# SparkFun_MegaShield.net
KiCad netlist of a schematic drawn in EAGLE
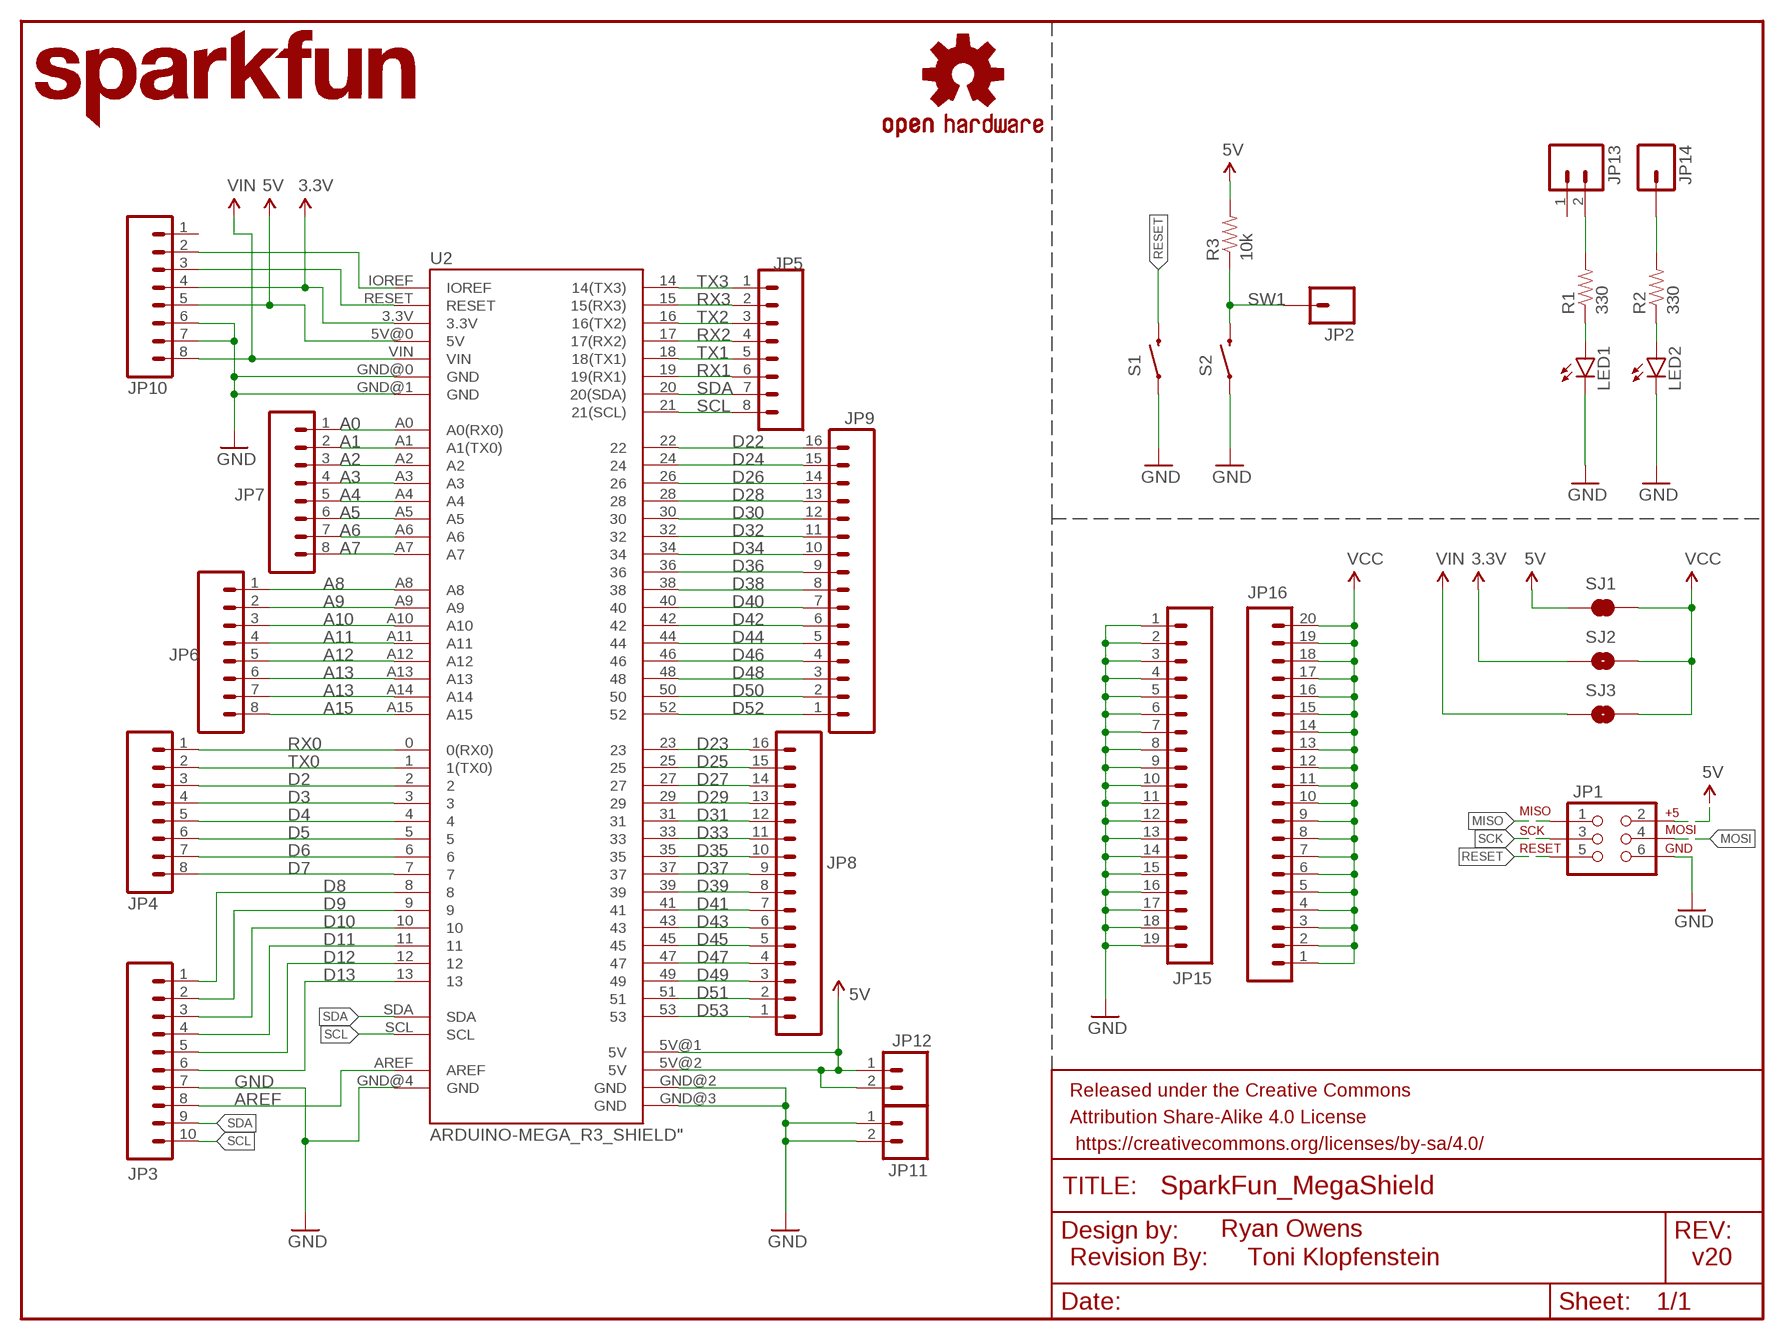
[diagram p0: schematic, sheet 1]

(export (version "E")
  (design (tool "Eeschema 10.0.6"))
  (components
    (comp (ref "FRAME1")
      (value "FRAME-LETTER")
      (footprint "eagle-import:CREATIVE_COMMONS")
      (libsource (lib "eagle-import") (part "FRAME-LETTER"))
    )
    (comp (ref "JP1")
      (value "AVR_SPI_PRG_6PTH")
      (footprint "eagle-import:2X3")
      (libsource (lib "eagle-import") (part "AVR_SPI_PRG_6PTH"))
    )
    (comp (ref "JP2")
      (value "M01PTH")
      (footprint "eagle-import:1X01")
      (libsource (lib "eagle-import") (part "M01PTH"))
    )
    (comp (ref "JP3")
      (value "M10SILK_FEMALE_PTH")
      (footprint "eagle-import:1X10")
      (libsource (lib "eagle-import") (part "M10SILK_FEMALE_PTH"))
    )
    (comp (ref "JP4")
      (value "M08")
      (footprint "eagle-import:1X08_ROUND")
      (libsource (lib "eagle-import") (part "M08"))
    )
    (comp (ref "JP5")
      (value "M08")
      (footprint "eagle-import:1X08_ROUND")
      (libsource (lib "eagle-import") (part "M08"))
    )
    (comp (ref "JP6")
      (value "M08")
      (footprint "eagle-import:1X08_ROUND")
      (libsource (lib "eagle-import") (part "M08"))
    )
    (comp (ref "JP7")
      (value "M08")
      (footprint "eagle-import:1X08_ROUND")
      (libsource (lib "eagle-import") (part "M08"))
    )
    (comp (ref "JP8")
      (value "M16PTH")
      (footprint "eagle-import:1X16")
      (libsource (lib "eagle-import") (part "M16PTH"))
    )
    (comp (ref "JP9")
      (value "M16PTH")
      (footprint "eagle-import:1X16")
      (libsource (lib "eagle-import") (part "M16PTH"))
    )
    (comp (ref "JP10")
      (value "M08")
      (footprint "eagle-import:1X08_ROUND")
      (libsource (lib "eagle-import") (part "M08"))
    )
    (comp (ref "JP11")
      (value "M02PTH")
      (footprint "eagle-import:1X02")
      (libsource (lib "eagle-import") (part "M02PTH"))
    )
    (comp (ref "JP12")
      (value "M02PTH")
      (footprint "eagle-import:1X02")
      (libsource (lib "eagle-import") (part "M02PTH"))
    )
    (comp (ref "JP13")
      (value "M02PTH")
      (footprint "eagle-import:1X02")
      (libsource (lib "eagle-import") (part "M02PTH"))
    )
    (comp (ref "JP14")
      (value "M01PTH")
      (footprint "eagle-import:1X01")
      (libsource (lib "eagle-import") (part "M01PTH"))
    )
    (comp (ref "JP15")
      (value "M191X19")
      (footprint "eagle-import:1X19")
      (libsource (lib "eagle-import") (part "M191X19"))
    )
    (comp (ref "JP16")
      (value "M20")
      (footprint "eagle-import:1X20")
      (libsource (lib "eagle-import") (part "M20"))
    )
    (comp (ref "LED1")
      (value "Red")
      (footprint "eagle-import:LED3MM")
      (libsource (lib "eagle-import") (part "LED3MM"))
    )
    (comp (ref "LED2")
      (value "Green")
      (footprint "eagle-import:LED3MM")
      (libsource (lib "eagle-import") (part "LED3MM"))
    )
    (comp (ref "LOGO1")
      (value "OSHW-LOGOS")
      (footprint "eagle-import:OSHW-LOGO-S")
      (libsource (lib "eagle-import") (part "OSHW-LOGOS"))
    )
    (comp (ref "LOGO2")
      (value "SFE_LOGO_NAME.1_INCH")
      (footprint "eagle-import:SFE_LOGO_NAME_.1")
      (libsource (lib "eagle-import") (part "SFE_LOGO_NAME.1_INCH"))
    )
    (comp (ref "R1")
      (value "330")
      (footprint "eagle-import:AXIAL-0.3")
      (libsource (lib "eagle-import") (part "RESISTORPTH1"))
    )
    (comp (ref "R2")
      (value "330")
      (footprint "eagle-import:AXIAL-0.3")
      (libsource (lib "eagle-import") (part "RESISTORPTH1"))
    )
    (comp (ref "R3")
      (value "10k")
      (footprint "eagle-import:AXIAL-0.3")
      (libsource (lib "eagle-import") (part "RESISTORPTH1"))
    )
    (comp (ref "S1")
      (value "SWITCH-MOMENTARY-2PTH")
      (footprint "eagle-import:TACTILE-PTH")
      (libsource (lib "eagle-import") (part "SWITCH-MOMENTARY-2PTH"))
    )
    (comp (ref "S2")
      (value "SWITCH-MOMENTARY-2PTH")
      (footprint "eagle-import:TACTILE-PTH")
      (libsource (lib "eagle-import") (part "SWITCH-MOMENTARY-2PTH"))
    )
    (comp (ref "SJ1")
      (value "JUMPER-PAD-2-NC_BY_TRACE")
      (footprint "eagle-import:PAD-JUMPER-2-NC_BY_TRACE_YES_SILK")
      (libsource (lib "eagle-import") (part "JUMPER-PAD-2-NC_BY_TRACE"))
    )
    (comp (ref "SJ2")
      (value "JUMPER-PAD-2-NOYES_SILK")
      (footprint "eagle-import:PAD-JUMPER-2-NO_YES_SILK")
      (libsource (lib "eagle-import") (part "JUMPER-PAD-2-NOYES_SILK"))
    )
    (comp (ref "SJ3")
      (value "JUMPER-PAD-2-NOYES_SILK")
      (footprint "eagle-import:PAD-JUMPER-2-NO_YES_SILK")
      (libsource (lib "eagle-import") (part "JUMPER-PAD-2-NOYES_SILK"))
    )
    (comp (ref "U$3")
      (value "REVISION")
      (footprint "eagle-import:REVISION")
      (libsource (lib "eagle-import") (part "REVISION"))
    )
    (comp (ref "U2")
      (value "ARDUINO-MEGA_R3_SHIELD\"")
      (footprint "eagle-import:ARDUINO_MEGA_R3_OUTLINE")
      (libsource (lib "eagle-import") (part "ARDUINO-MEGA_R3_SHIELD{dblquote}"))
    )
  )
  (nets
    (net (code "1") (name "/A0") (class "Default")
      (node (ref "JP7") (pin "1") (pinfunction "1_1") (pintype "passive"))
      (node (ref "U2") (pin "A0") (pinfunction "A0(RX0)_A0") (pintype "bidirectional"))
    )
    (net (code "2") (name "/A1") (class "Default")
      (node (ref "JP7") (pin "2") (pinfunction "2_2") (pintype "passive"))
      (node (ref "U2") (pin "A1") (pinfunction "A1(TX0)_A1") (pintype "bidirectional"))
    )
    (net (code "3") (name "/A2") (class "Default")
      (node (ref "JP7") (pin "3") (pinfunction "3_3") (pintype "passive"))
      (node (ref "U2") (pin "A2") (pinfunction "A2_A2") (pintype "bidirectional"))
    )
    (net (code "4") (name "/A3") (class "Default")
      (node (ref "JP7") (pin "4") (pinfunction "4_4") (pintype "passive"))
      (node (ref "U2") (pin "A3") (pinfunction "A3_A3") (pintype "bidirectional"))
    )
    (net (code "5") (name "/A4") (class "Default")
      (node (ref "JP7") (pin "5") (pinfunction "5_5") (pintype "passive"))
      (node (ref "U2") (pin "A4") (pinfunction "A4_A4") (pintype "bidirectional"))
    )
    (net (code "6") (name "/A5") (class "Default")
      (node (ref "JP7") (pin "6") (pinfunction "6_6") (pintype "passive"))
      (node (ref "U2") (pin "A5") (pinfunction "A5_A5") (pintype "bidirectional"))
    )
    (net (code "7") (name "/A6") (class "Default")
      (node (ref "JP7") (pin "7") (pinfunction "7_7") (pintype "passive"))
      (node (ref "U2") (pin "A6") (pinfunction "A6_A6") (pintype "bidirectional"))
    )
    (net (code "8") (name "/A7") (class "Default")
      (node (ref "JP7") (pin "8") (pinfunction "8_8") (pintype "passive"))
      (node (ref "U2") (pin "A7") (pinfunction "A7_A7") (pintype "bidirectional"))
    )
    (net (code "9") (name "/A8") (class "Default")
      (node (ref "JP6") (pin "1") (pinfunction "1_1") (pintype "passive"))
      (node (ref "U2") (pin "A8") (pinfunction "A8_A8") (pintype "bidirectional"))
    )
    (net (code "10") (name "/A9") (class "Default")
      (node (ref "JP6") (pin "2") (pinfunction "2_2") (pintype "passive"))
      (node (ref "U2") (pin "A9") (pinfunction "A9_A9") (pintype "bidirectional"))
    )
    (net (code "11") (name "/A10") (class "Default")
      (node (ref "JP6") (pin "3") (pinfunction "3_3") (pintype "passive"))
      (node (ref "U2") (pin "A10") (pinfunction "A10_A10") (pintype "bidirectional"))
    )
    (net (code "12") (name "/A11") (class "Default")
      (node (ref "JP6") (pin "4") (pinfunction "4_4") (pintype "passive"))
      (node (ref "U2") (pin "A11") (pinfunction "A11_A11") (pintype "bidirectional"))
    )
    (net (code "13") (name "/A12") (class "Default")
      (node (ref "JP6") (pin "5") (pinfunction "5_5") (pintype "passive"))
      (node (ref "U2") (pin "A12") (pinfunction "A12_A12") (pintype "bidirectional"))
    )
    (net (code "14") (name "/A13") (class "Default")
      (node (ref "JP6") (pin "6") (pinfunction "6_6") (pintype "passive"))
      (node (ref "U2") (pin "A13") (pinfunction "A13_A13") (pintype "bidirectional"))
    )
    (net (code "15") (name "/A15") (class "Default")
      (node (ref "JP6") (pin "8") (pinfunction "8_8") (pintype "passive"))
      (node (ref "U2") (pin "A15") (pinfunction "A15_A15") (pintype "bidirectional"))
    )
    (net (code "16") (name "/AREF") (class "Default")
      (node (ref "JP3") (pin "8") (pinfunction "8_8") (pintype "passive"))
      (node (ref "U2") (pin "AREF") (pinfunction "AREF_AREF") (pintype "bidirectional"))
    )
    (net (code "17") (name "/D2") (class "Default")
      (node (ref "JP4") (pin "3") (pinfunction "3_3") (pintype "passive"))
      (node (ref "U2") (pin "2") (pinfunction "2_2") (pintype "bidirectional"))
    )
    (net (code "18") (name "/D3") (class "Default")
      (node (ref "JP4") (pin "4") (pinfunction "4_4") (pintype "passive"))
      (node (ref "U2") (pin "3") (pinfunction "3_3") (pintype "bidirectional"))
    )
    (net (code "19") (name "/D4") (class "Default")
      (node (ref "JP4") (pin "5") (pinfunction "5_5") (pintype "passive"))
      (node (ref "U2") (pin "4") (pinfunction "4_4") (pintype "bidirectional"))
    )
    (net (code "20") (name "/D5") (class "Default")
      (node (ref "JP4") (pin "6") (pinfunction "6_6") (pintype "passive"))
      (node (ref "U2") (pin "5") (pinfunction "5_5") (pintype "bidirectional"))
    )
    (net (code "21") (name "/D6") (class "Default")
      (node (ref "JP4") (pin "7") (pinfunction "7_7") (pintype "passive"))
      (node (ref "U2") (pin "6") (pinfunction "6_6") (pintype "bidirectional"))
    )
    (net (code "22") (name "/D7") (class "Default")
      (node (ref "JP4") (pin "8") (pinfunction "8_8") (pintype "passive"))
      (node (ref "U2") (pin "7") (pinfunction "7_7") (pintype "bidirectional"))
    )
    (net (code "23") (name "/D8") (class "Default")
      (node (ref "JP3") (pin "1") (pinfunction "1_1") (pintype "passive"))
      (node (ref "U2") (pin "8") (pinfunction "8_8") (pintype "bidirectional"))
    )
    (net (code "24") (name "/D9") (class "Default")
      (node (ref "JP3") (pin "2") (pinfunction "2_2") (pintype "passive"))
      (node (ref "U2") (pin "9") (pinfunction "9_9") (pintype "bidirectional"))
    )
    (net (code "25") (name "/D10") (class "Default")
      (node (ref "JP3") (pin "3") (pinfunction "3_3") (pintype "passive"))
      (node (ref "U2") (pin "10") (pinfunction "10_10") (pintype "bidirectional"))
    )
    (net (code "26") (name "/D11") (class "Default")
      (node (ref "JP3") (pin "4") (pinfunction "4_4") (pintype "passive"))
      (node (ref "U2") (pin "11") (pinfunction "11_11") (pintype "bidirectional"))
    )
    (net (code "27") (name "/D12") (class "Default")
      (node (ref "JP3") (pin "5") (pinfunction "5_5") (pintype "passive"))
      (node (ref "U2") (pin "12") (pinfunction "12_12") (pintype "bidirectional"))
    )
    (net (code "28") (name "/D13") (class "Default")
      (node (ref "JP3") (pin "6") (pinfunction "6_6") (pintype "passive"))
      (node (ref "U2") (pin "13") (pinfunction "13_13") (pintype "bidirectional"))
    )
    (net (code "29") (name "/D22") (class "Default")
      (node (ref "JP9") (pin "16") (pinfunction "16_16") (pintype "passive"))
      (node (ref "U2") (pin "22") (pinfunction "22_22") (pintype "bidirectional"))
    )
    (net (code "30") (name "/D23") (class "Default")
      (node (ref "JP8") (pin "16") (pinfunction "16_16") (pintype "passive"))
      (node (ref "U2") (pin "23") (pinfunction "23_23") (pintype "bidirectional"))
    )
    (net (code "31") (name "/D24") (class "Default")
      (node (ref "JP9") (pin "15") (pinfunction "15_15") (pintype "passive"))
      (node (ref "U2") (pin "24") (pinfunction "24_24") (pintype "bidirectional"))
    )
    (net (code "32") (name "/D25") (class "Default")
      (node (ref "JP8") (pin "15") (pinfunction "15_15") (pintype "passive"))
      (node (ref "U2") (pin "25") (pinfunction "25_25") (pintype "bidirectional"))
    )
    (net (code "33") (name "/D26") (class "Default")
      (node (ref "JP9") (pin "14") (pinfunction "14_14") (pintype "passive"))
      (node (ref "U2") (pin "26") (pinfunction "26_26") (pintype "bidirectional"))
    )
    (net (code "34") (name "/D27") (class "Default")
      (node (ref "JP8") (pin "14") (pinfunction "14_14") (pintype "passive"))
      (node (ref "U2") (pin "27") (pinfunction "27_27") (pintype "bidirectional"))
    )
    (net (code "35") (name "/D28") (class "Default")
      (node (ref "JP9") (pin "13") (pinfunction "13_13") (pintype "passive"))
      (node (ref "U2") (pin "28") (pinfunction "28_28") (pintype "bidirectional"))
    )
    (net (code "36") (name "/D29") (class "Default")
      (node (ref "JP8") (pin "13") (pinfunction "13_13") (pintype "passive"))
      (node (ref "U2") (pin "29") (pinfunction "29_29") (pintype "bidirectional"))
    )
    (net (code "37") (name "/D30") (class "Default")
      (node (ref "JP9") (pin "12") (pinfunction "12_12") (pintype "passive"))
      (node (ref "U2") (pin "30") (pinfunction "30_30") (pintype "bidirectional"))
    )
    (net (code "38") (name "/D31") (class "Default")
      (node (ref "JP8") (pin "12") (pinfunction "12_12") (pintype "passive"))
      (node (ref "U2") (pin "31") (pinfunction "31_31") (pintype "bidirectional"))
    )
    (net (code "39") (name "/D32") (class "Default")
      (node (ref "JP9") (pin "11") (pinfunction "11_11") (pintype "passive"))
      (node (ref "U2") (pin "32") (pinfunction "32_32") (pintype "bidirectional"))
    )
    (net (code "40") (name "/D33") (class "Default")
      (node (ref "JP8") (pin "11") (pinfunction "11_11") (pintype "passive"))
      (node (ref "U2") (pin "33") (pinfunction "33_33") (pintype "bidirectional"))
    )
    (net (code "41") (name "/D34") (class "Default")
      (node (ref "JP9") (pin "10") (pinfunction "10_10") (pintype "passive"))
      (node (ref "U2") (pin "34") (pinfunction "34_34") (pintype "bidirectional"))
    )
    (net (code "42") (name "/D35") (class "Default")
      (node (ref "JP8") (pin "10") (pinfunction "10_10") (pintype "passive"))
      (node (ref "U2") (pin "35") (pinfunction "35_35") (pintype "bidirectional"))
    )
    (net (code "43") (name "/D36") (class "Default")
      (node (ref "JP9") (pin "9") (pinfunction "9_9") (pintype "passive"))
      (node (ref "U2") (pin "36") (pinfunction "36_36") (pintype "bidirectional"))
    )
    (net (code "44") (name "/D37") (class "Default")
      (node (ref "JP8") (pin "9") (pinfunction "9_9") (pintype "passive"))
      (node (ref "U2") (pin "37") (pinfunction "37_37") (pintype "bidirectional"))
    )
    (net (code "45") (name "/D38") (class "Default")
      (node (ref "JP9") (pin "8") (pinfunction "8_8") (pintype "passive"))
      (node (ref "U2") (pin "38") (pinfunction "38_38") (pintype "bidirectional"))
    )
    (net (code "46") (name "/D39") (class "Default")
      (node (ref "JP8") (pin "8") (pinfunction "8_8") (pintype "passive"))
      (node (ref "U2") (pin "39") (pinfunction "39_39") (pintype "bidirectional"))
    )
    (net (code "47") (name "/D40") (class "Default")
      (node (ref "JP9") (pin "7") (pinfunction "7_7") (pintype "passive"))
      (node (ref "U2") (pin "40") (pinfunction "40_40") (pintype "bidirectional"))
    )
    (net (code "48") (name "/D41") (class "Default")
      (node (ref "JP8") (pin "7") (pinfunction "7_7") (pintype "passive"))
      (node (ref "U2") (pin "41") (pinfunction "41_41") (pintype "bidirectional"))
    )
    (net (code "49") (name "/D42") (class "Default")
      (node (ref "JP9") (pin "6") (pinfunction "6_6") (pintype "passive"))
      (node (ref "U2") (pin "42") (pinfunction "42_42") (pintype "bidirectional"))
    )
    (net (code "50") (name "/D43") (class "Default")
      (node (ref "JP8") (pin "6") (pinfunction "6_6") (pintype "passive"))
      (node (ref "U2") (pin "43") (pinfunction "43_43") (pintype "bidirectional"))
    )
    (net (code "51") (name "/D44") (class "Default")
      (node (ref "JP9") (pin "5") (pinfunction "5_5") (pintype "passive"))
      (node (ref "U2") (pin "44") (pinfunction "44_44") (pintype "bidirectional"))
    )
    (net (code "52") (name "/D45") (class "Default")
      (node (ref "JP8") (pin "5") (pinfunction "5_5") (pintype "passive"))
      (node (ref "U2") (pin "45") (pinfunction "45_45") (pintype "bidirectional"))
    )
    (net (code "53") (name "/D46") (class "Default")
      (node (ref "JP9") (pin "4") (pinfunction "4_4") (pintype "passive"))
      (node (ref "U2") (pin "46") (pinfunction "46_46") (pintype "bidirectional"))
    )
    (net (code "54") (name "/D47") (class "Default")
      (node (ref "JP8") (pin "4") (pinfunction "4_4") (pintype "passive"))
      (node (ref "U2") (pin "47") (pinfunction "47_47") (pintype "bidirectional"))
    )
    (net (code "55") (name "/D48") (class "Default")
      (node (ref "JP9") (pin "3") (pinfunction "3_3") (pintype "passive"))
      (node (ref "U2") (pin "48") (pinfunction "48_48") (pintype "bidirectional"))
    )
    (net (code "56") (name "/D49") (class "Default")
      (node (ref "JP8") (pin "3") (pinfunction "3_3") (pintype "passive"))
      (node (ref "U2") (pin "49") (pinfunction "49_49") (pintype "bidirectional"))
    )
    (net (code "57") (name "/D50") (class "Default")
      (node (ref "JP9") (pin "2") (pinfunction "2_2") (pintype "passive"))
      (node (ref "U2") (pin "50") (pinfunction "50_50") (pintype "bidirectional"))
    )
    (net (code "58") (name "/D51") (class "Default")
      (node (ref "JP8") (pin "2") (pinfunction "2_2") (pintype "passive"))
      (node (ref "U2") (pin "51") (pinfunction "51_51") (pintype "bidirectional"))
    )
    (net (code "59") (name "/D52") (class "Default")
      (node (ref "JP9") (pin "1") (pinfunction "1_1") (pintype "passive"))
      (node (ref "U2") (pin "52") (pinfunction "52_52") (pintype "bidirectional"))
    )
    (net (code "60") (name "/D53") (class "Default")
      (node (ref "JP8") (pin "1") (pinfunction "1_1") (pintype "passive"))
      (node (ref "U2") (pin "53") (pinfunction "53_53") (pintype "bidirectional"))
    )
    (net (code "61") (name "/RX0") (class "Default")
      (node (ref "JP4") (pin "1") (pinfunction "1_1") (pintype "passive"))
      (node (ref "U2") (pin "0") (pinfunction "0(RX0)_0") (pintype "bidirectional"))
    )
    (net (code "62") (name "/RX1") (class "Default")
      (node (ref "JP5") (pin "6") (pinfunction "6_6") (pintype "passive"))
      (node (ref "U2") (pin "19") (pinfunction "19(RX1)_19") (pintype "bidirectional"))
    )
    (net (code "63") (name "/RX2") (class "Default")
      (node (ref "JP5") (pin "4") (pinfunction "4_4") (pintype "passive"))
      (node (ref "U2") (pin "17") (pinfunction "17(RX2)_17") (pintype "bidirectional"))
    )
    (net (code "64") (name "/RX3") (class "Default")
      (node (ref "JP5") (pin "2") (pinfunction "2_2") (pintype "passive"))
      (node (ref "U2") (pin "15") (pinfunction "15(RX3)_15") (pintype "bidirectional"))
    )
    (net (code "65") (name "/SW1") (class "Default")
      (node (ref "JP2") (pin "1") (pinfunction "1_1") (pintype "passive"))
      (node (ref "R3") (pin "P$1") (pinfunction "1_P$1") (pintype "passive"))
      (node (ref "S2") (pin "3") (pinfunction "2_3") (pintype "passive"))
    )
    (net (code "66") (name "/TX0") (class "Default")
      (node (ref "JP4") (pin "2") (pinfunction "2_2") (pintype "passive"))
      (node (ref "U2") (pin "1") (pinfunction "1(TX0)_1") (pintype "bidirectional"))
    )
    (net (code "67") (name "/TX1") (class "Default")
      (node (ref "JP5") (pin "5") (pinfunction "5_5") (pintype "passive"))
      (node (ref "U2") (pin "18") (pinfunction "18(TX1)_18") (pintype "bidirectional"))
    )
    (net (code "68") (name "/TX2") (class "Default")
      (node (ref "JP5") (pin "3") (pinfunction "3_3") (pintype "passive"))
      (node (ref "U2") (pin "16") (pinfunction "16(TX2)_16") (pintype "bidirectional"))
    )
    (net (code "69") (name "/TX3") (class "Default")
      (node (ref "JP5") (pin "1") (pinfunction "1_1") (pintype "passive"))
      (node (ref "U2") (pin "14") (pinfunction "14(TX3)_14") (pintype "bidirectional"))
    )
    (net (code "70") (name "3.3V") (class "Default")
      (node (ref "JP10") (pin "4") (pinfunction "4_4") (pintype "passive"))
      (node (ref "SJ2") (pin "1") (pinfunction "1_1") (pintype "passive"))
      (node (ref "U2") (pin "3.3V") (pinfunction "3.3V_3.3V") (pintype "bidirectional"))
    )
    (net (code "71") (name "5V") (class "Default")
      (node (ref "JP1") (pin "2") (pinfunction "2_2") (pintype "passive"))
      (node (ref "JP10") (pin "5") (pinfunction "5_5") (pintype "passive"))
      (node (ref "JP12") (pin "1") (pinfunction "1_1") (pintype "passive"))
      (node (ref "JP12") (pin "2") (pinfunction "2_2") (pintype "passive"))
      (node (ref "R3") (pin "P$2") (pinfunction "2_P$2") (pintype "passive"))
      (node (ref "SJ1") (pin "1") (pinfunction "1_1") (pintype "passive"))
      (node (ref "U2") (pin "5V@0") (pinfunction "5V_5V@0") (pintype "bidirectional"))
      (node (ref "U2") (pin "5V@1") (pinfunction "5V_5V@1") (pintype "bidirectional"))
      (node (ref "U2") (pin "5V@2") (pinfunction "5V_5V@2") (pintype "bidirectional"))
    )
    (net (code "72") (name "GND") (class "Default")
      (node (ref "JP1") (pin "6") (pinfunction "6_6") (pintype "passive"))
      (node (ref "JP10") (pin "6") (pinfunction "6_6") (pintype "passive"))
      (node (ref "JP10") (pin "7") (pinfunction "7_7") (pintype "passive"))
      (node (ref "JP11") (pin "1") (pinfunction "1_1") (pintype "passive"))
      (node (ref "JP11") (pin "2") (pinfunction "2_2") (pintype "passive"))
      (node (ref "JP15") (pin "1") (pinfunction "1_1") (pintype "passive"))
      (node (ref "JP15") (pin "10") (pinfunction "10_10") (pintype "passive"))
      (node (ref "JP15") (pin "11") (pinfunction "11_11") (pintype "passive"))
      (node (ref "JP15") (pin "12") (pinfunction "12_12") (pintype "passive"))
      (node (ref "JP15") (pin "13") (pinfunction "13_13") (pintype "passive"))
      (node (ref "JP15") (pin "14") (pinfunction "14_14") (pintype "passive"))
      (node (ref "JP15") (pin "15") (pinfunction "15_15") (pintype "passive"))
      (node (ref "JP15") (pin "16") (pinfunction "16_16") (pintype "passive"))
      (node (ref "JP15") (pin "17") (pinfunction "17_17") (pintype "passive"))
      (node (ref "JP15") (pin "18") (pinfunction "18_18") (pintype "passive"))
      (node (ref "JP15") (pin "19") (pinfunction "19_19") (pintype "passive"))
      (node (ref "JP15") (pin "2") (pinfunction "2_2") (pintype "passive"))
      (node (ref "JP15") (pin "3") (pinfunction "3_3") (pintype "passive"))
      (node (ref "JP15") (pin "4") (pinfunction "4_4") (pintype "passive"))
      (node (ref "JP15") (pin "5") (pinfunction "5_5") (pintype "passive"))
      (node (ref "JP15") (pin "6") (pinfunction "6_6") (pintype "passive"))
      (node (ref "JP15") (pin "7") (pinfunction "7_7") (pintype "passive"))
      (node (ref "JP15") (pin "8") (pinfunction "8_8") (pintype "passive"))
      (node (ref "JP15") (pin "9") (pinfunction "9_9") (pintype "passive"))
      (node (ref "JP3") (pin "7") (pinfunction "7_7") (pintype "passive"))
      (node (ref "LED1") (pin "K") (pinfunction "C_K") (pintype "passive"))
      (node (ref "LED2") (pin "K") (pinfunction "C_K") (pintype "passive"))
      (node (ref "S1") (pin "1") (pinfunction "1_1") (pintype "passive"))
      (node (ref "S2") (pin "1") (pinfunction "1_1") (pintype "passive"))
      (node (ref "U2") (pin "GND@0") (pinfunction "GND_GND@0") (pintype "bidirectional"))
      (node (ref "U2") (pin "GND@1") (pinfunction "GND_GND@1") (pintype "bidirectional"))
      (node (ref "U2") (pin "GND@2") (pinfunction "GND_GND@2") (pintype "bidirectional"))
      (node (ref "U2") (pin "GND@3") (pinfunction "GND_GND@3") (pintype "bidirectional"))
      (node (ref "U2") (pin "GND@4") (pinfunction "GND_GND@4") (pintype "bidirectional"))
    )
    (net (code "73") (name "MISO") (class "Default")
      (node (ref "JP1") (pin "1") (pinfunction "1_1") (pintype "passive"))
    )
    (net (code "74") (name "MOSI") (class "Default")
      (node (ref "JP1") (pin "4") (pinfunction "4_4") (pintype "passive"))
    )
    (net (code "75") (name "Net-(JP6-Pad7)") (class "Default")
      (node (ref "JP6") (pin "7") (pinfunction "7_7") (pintype "passive"))
      (node (ref "U2") (pin "A14") (pinfunction "A14_A14") (pintype "bidirectional"))
    )
    (net (code "76") (name "Net-(JP10-Pad2)") (class "Default")
      (node (ref "JP10") (pin "2") (pinfunction "2_2") (pintype "passive"))
      (node (ref "U2") (pin "IOREF") (pinfunction "IOREF_IOREF") (pintype "bidirectional"))
    )
    (net (code "77") (name "Net-(R1-1)") (class "Default")
      (node (ref "LED1") (pin "A") (pinfunction "A_A") (pintype "passive"))
      (node (ref "R1") (pin "P$1") (pinfunction "1_P$1") (pintype "passive"))
    )
    (net (code "78") (name "Net-(R1-2)") (class "Default")
      (node (ref "JP13") (pin "2") (pinfunction "2_2") (pintype "passive"))
      (node (ref "R1") (pin "P$2") (pinfunction "2_P$2") (pintype "passive"))
    )
    (net (code "79") (name "Net-(R2-1)") (class "Default")
      (node (ref "LED2") (pin "A") (pinfunction "A_A") (pintype "passive"))
      (node (ref "R2") (pin "P$1") (pinfunction "1_P$1") (pintype "passive"))
    )
    (net (code "80") (name "Net-(R2-2)") (class "Default")
      (node (ref "JP14") (pin "1") (pinfunction "1_1") (pintype "passive"))
      (node (ref "R2") (pin "P$2") (pinfunction "2_P$2") (pintype "passive"))
    )
    (net (code "81") (name "RESET") (class "Default")
      (node (ref "JP1") (pin "5") (pinfunction "5_5") (pintype "passive"))
      (node (ref "JP10") (pin "3") (pinfunction "3_3") (pintype "passive"))
      (node (ref "S1") (pin "3") (pinfunction "2_3") (pintype "passive"))
      (node (ref "U2") (pin "RESET") (pinfunction "RESET_RESET") (pintype "bidirectional"))
    )
    (net (code "82") (name "SCK") (class "Default")
      (node (ref "JP1") (pin "3") (pinfunction "3_3") (pintype "passive"))
    )
    (net (code "83") (name "SCL") (class "Default")
      (node (ref "JP3") (pin "10") (pinfunction "10_10") (pintype "passive"))
      (node (ref "JP5") (pin "8") (pinfunction "8_8") (pintype "passive"))
      (node (ref "U2") (pin "21") (pinfunction "21(SCL)_21") (pintype "bidirectional"))
      (node (ref "U2") (pin "SCL") (pinfunction "SCL_SCL") (pintype "bidirectional"))
    )
    (net (code "84") (name "SDA") (class "Default")
      (node (ref "JP3") (pin "9") (pinfunction "9_9") (pintype "passive"))
      (node (ref "JP5") (pin "7") (pinfunction "7_7") (pintype "passive"))
      (node (ref "U2") (pin "20") (pinfunction "20(SDA)_20") (pintype "bidirectional"))
      (node (ref "U2") (pin "SDA") (pinfunction "SDA_SDA") (pintype "bidirectional"))
    )
    (net (code "85") (name "VCC") (class "Default")
      (node (ref "JP16") (pin "1") (pinfunction "1_1") (pintype "passive"))
      (node (ref "JP16") (pin "10") (pinfunction "10_10") (pintype "passive"))
      (node (ref "JP16") (pin "11") (pinfunction "11_11") (pintype "passive"))
      (node (ref "JP16") (pin "12") (pinfunction "12_12") (pintype "passive"))
      (node (ref "JP16") (pin "13") (pinfunction "13_13") (pintype "passive"))
      (node (ref "JP16") (pin "14") (pinfunction "14_14") (pintype "passive"))
      (node (ref "JP16") (pin "15") (pinfunction "15_15") (pintype "passive"))
      (node (ref "JP16") (pin "16") (pinfunction "16_16") (pintype "passive"))
      (node (ref "JP16") (pin "17") (pinfunction "17_17") (pintype "passive"))
      (node (ref "JP16") (pin "18") (pinfunction "18_18") (pintype "passive"))
      (node (ref "JP16") (pin "19") (pinfunction "19_19") (pintype "passive"))
      (node (ref "JP16") (pin "2") (pinfunction "2_2") (pintype "passive"))
      (node (ref "JP16") (pin "20") (pinfunction "20_20") (pintype "passive"))
      (node (ref "JP16") (pin "3") (pinfunction "3_3") (pintype "passive"))
      (node (ref "JP16") (pin "4") (pinfunction "4_4") (pintype "passive"))
      (node (ref "JP16") (pin "5") (pinfunction "5_5") (pintype "passive"))
      (node (ref "JP16") (pin "6") (pinfunction "6_6") (pintype "passive"))
      (node (ref "JP16") (pin "7") (pinfunction "7_7") (pintype "passive"))
      (node (ref "JP16") (pin "8") (pinfunction "8_8") (pintype "passive"))
      (node (ref "JP16") (pin "9") (pinfunction "9_9") (pintype "passive"))
      (node (ref "SJ1") (pin "2") (pinfunction "2_2") (pintype "passive"))
      (node (ref "SJ2") (pin "2") (pinfunction "2_2") (pintype "passive"))
      (node (ref "SJ3") (pin "2") (pinfunction "2_2") (pintype "passive"))
    )
    (net (code "86") (name "VIN") (class "Default")
      (node (ref "JP10") (pin "8") (pinfunction "8_8") (pintype "passive"))
      (node (ref "SJ3") (pin "1") (pinfunction "1_1") (pintype "passive"))
      (node (ref "U2") (pin "VIN") (pinfunction "VIN_VIN") (pintype "bidirectional"))
    )
    (net (code "87") (name "unconnected-(JP10-Pad1)") (class "Default")
      (node (ref "JP10") (pin "1") (pinfunction "1_1") (pintype "passive"))
    )
    (net (code "88") (name "unconnected-(JP13-Pad1)") (class "Default")
      (node (ref "JP13") (pin "1") (pinfunction "1_1") (pintype "passive"))
    )
  )
)
